# ups_main.net
KiCad netlist of a schematic drawn in EAGLE
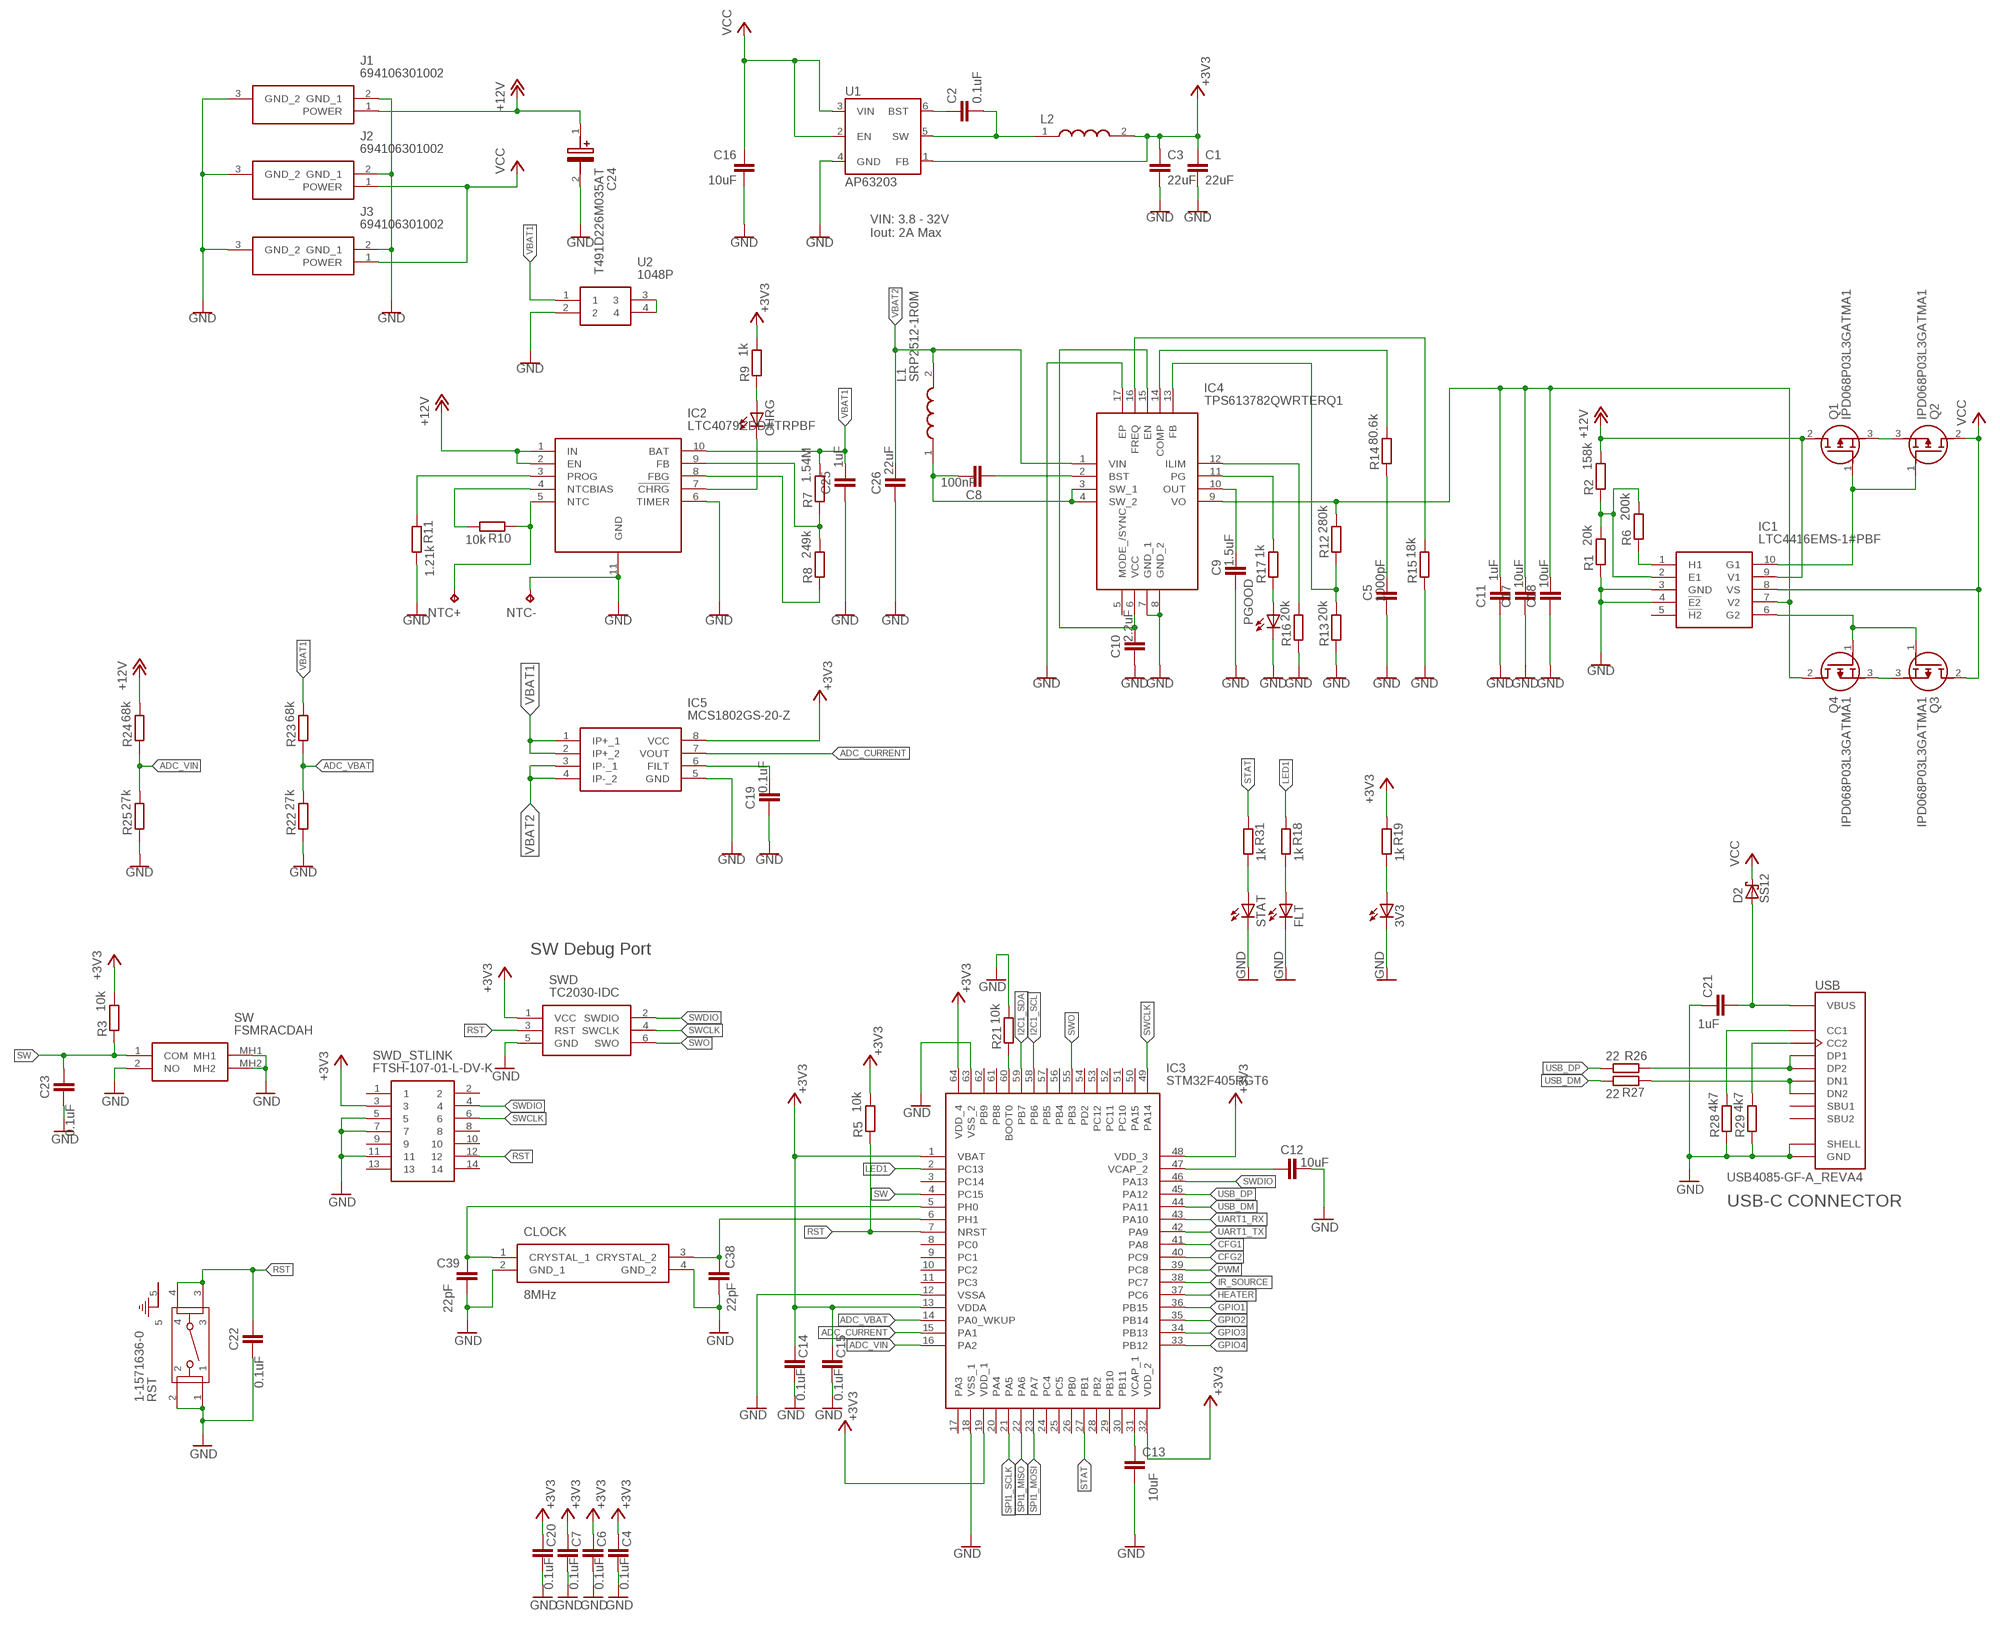
[diagram p0: schematic, sheet 1]

(export (version "E")
  (design (tool "Eeschema 10.0.6"))
  (components
    (comp (ref "3V3")
      (value "LEDCHIPLED_0805")
      (footprint "eagle-import:CHIPLED_0805")
      (libsource (lib "eagle-import") (part "LEDCHIPLED_0805"))
    )
    (comp (ref "C1")
      (value "22uF")
      (footprint "eagle-import:0603")
      (libsource (lib "eagle-import") (part "22UF-0603-6.3V-20%"))
    )
    (comp (ref "C2")
      (value "0.1uF")
      (footprint "eagle-import:0603")
      (libsource (lib "eagle-import") (part "0.1UF-0603-25V-5%"))
    )
    (comp (ref "C3")
      (value "22uF")
      (footprint "eagle-import:0603")
      (libsource (lib "eagle-import") (part "22UF-0603-6.3V-20%"))
    )
    (comp (ref "C4")
      (value "0.1uF")
      (footprint "eagle-import:C0603K")
      (libsource (lib "eagle-import") (part "C-EUC0603K"))
    )
    (comp (ref "C5")
      (value "1000pF")
      (footprint "eagle-import:C0603K")
      (libsource (lib "eagle-import") (part "C-EUC0603K"))
    )
    (comp (ref "C6")
      (value "0.1uF")
      (footprint "eagle-import:C0603K")
      (libsource (lib "eagle-import") (part "C-EUC0603K"))
    )
    (comp (ref "C7")
      (value "0.1uF")
      (footprint "eagle-import:C0603K")
      (libsource (lib "eagle-import") (part "C-EUC0603K"))
    )
    (comp (ref "C8")
      (value "100nF")
      (footprint "eagle-import:C0603K")
      (libsource (lib "eagle-import") (part "C-EUC0603K"))
    )
    (comp (ref "C9")
      (value "1.5uF")
      (footprint "eagle-import:C0603K")
      (libsource (lib "eagle-import") (part "C-EUC0603K"))
    )
    (comp (ref "C10")
      (value "2.2uF")
      (footprint "eagle-import:C0603K")
      (libsource (lib "eagle-import") (part "C-EUC0603K"))
    )
    (comp (ref "C11")
      (value "1uF")
      (footprint "eagle-import:C0603K")
      (libsource (lib "eagle-import") (part "C-EUC0603K"))
    )
    (comp (ref "C12")
      (value "10uF")
      (footprint "eagle-import:C0603K")
      (libsource (lib "eagle-import") (part "C-EUC0603K"))
    )
    (comp (ref "C13")
      (value "10uF")
      (footprint "eagle-import:C0603K")
      (libsource (lib "eagle-import") (part "C-EUC0603K"))
    )
    (comp (ref "C14")
      (value "0.1uF")
      (footprint "eagle-import:C0603K")
      (libsource (lib "eagle-import") (part "C-EUC0603K"))
    )
    (comp (ref "C15")
      (value "0.1uF")
      (footprint "eagle-import:C0603K")
      (libsource (lib "eagle-import") (part "C-EUC0603K"))
    )
    (comp (ref "C16")
      (value "10uF")
      (footprint "eagle-import:1210")
      (libsource (lib "eagle-import") (part "10UF-1210-50V-20%"))
    )
    (comp (ref "C17")
      (value "10uF")
      (footprint "eagle-import:C0603K")
      (libsource (lib "eagle-import") (part "C-EUC0603K"))
    )
    (comp (ref "C18")
      (value "10uF")
      (footprint "eagle-import:C0603K")
      (libsource (lib "eagle-import") (part "C-EUC0603K"))
    )
    (comp (ref "C19")
      (value "0.1uF")
      (footprint "eagle-import:C0603K")
      (libsource (lib "eagle-import") (part "C-EUC0603K"))
    )
    (comp (ref "C20")
      (value "0.1uF")
      (footprint "eagle-import:C0603K")
      (libsource (lib "eagle-import") (part "C-EUC0603K"))
    )
    (comp (ref "C21")
      (value "1uF")
      (footprint "eagle-import:C0603K")
      (libsource (lib "eagle-import") (part "C-EUC0603K"))
    )
    (comp (ref "C22")
      (value "0.1uF")
      (footprint "eagle-import:C0603K")
      (libsource (lib "eagle-import") (part "C-EUC0603K"))
    )
    (comp (ref "C23")
      (value "0.1uF")
      (footprint "eagle-import:C0603K")
      (libsource (lib "eagle-import") (part "C-EUC0603K"))
    )
    (comp (ref "C24")
      (value "T491D226M035AT")
      (footprint "eagle-import:T491D")
      (fields (field (name "MOUSER_PART_NUMBER") "80-T491D226M035"))
      (libsource (lib "eagle-import") (part "T491D226M035AT"))
    )
    (comp (ref "C25")
      (value "1uF")
      (footprint "eagle-import:C0603K")
      (libsource (lib "eagle-import") (part "C-EUC0603K"))
    )
    (comp (ref "C26")
      (value "22uF")
      (footprint "eagle-import:C0603K")
      (libsource (lib "eagle-import") (part "C-EUC0603K"))
    )
    (comp (ref "C38")
      (value "22pF")
      (footprint "eagle-import:C0603K")
      (libsource (lib "eagle-import") (part "C-EUC0603K"))
    )
    (comp (ref "C39")
      (value "22pF")
      (footprint "eagle-import:C0603K")
      (libsource (lib "eagle-import") (part "C-EUC0603K"))
    )
    (comp (ref "CHRG")
      (value "LEDCHIPLED_0805")
      (footprint "eagle-import:CHIPLED_0805")
      (libsource (lib "eagle-import") (part "LEDCHIPLED_0805"))
    )
    (comp (ref "CLOCK")
      (value "8MHz")
      (footprint "eagle-import:ABM8AIG8000MHZ1ZT")
      (fields
        (field (name "MANUFACTURER_PART_NUMBER") "ABM8AIG-8.000MHZ-1Z-T")
        (field (name "MOUSER_PART_NUMBER") "815-M8AIG-8-1ZT")
      )
      (libsource (lib "eagle-import") (part "ABM8AIG-8.000MHZ-1Z-T"))
    )
    (comp (ref "D2")
      (value "SS12")
      (footprint "eagle-import:DO214AC")
      (fields (field (name "MF") "Klein Tools,"))
      (libsource (lib "eagle-import") (part "SS12"))
    )
    (comp (ref "FLT")
      (value "LEDCHIPLED_0805")
      (footprint "eagle-import:CHIPLED_0805")
      (libsource (lib "eagle-import") (part "LEDCHIPLED_0805"))
    )
    (comp (ref "IC1")
      (value "LTC4416EMS-1#PBF")
      (footprint "eagle-import:SOP50P490X110-10N")
      (fields (field (name "MOUSER_PART_NUMBER") "584-LTC4416EMS-1#PBF"))
      (libsource (lib "eagle-import") (part "LTC4416EMS-1#PBF"))
    )
    (comp (ref "IC2")
      (value "LTC4079EDD#TRPBF")
      (footprint "eagle-import:SON50P300X300X80-11N")
      (fields (field (name "MOUSER_PART_NUMBER") "584-LTC4079EDD#TRPBF"))
      (libsource (lib "eagle-import") (part "LTC4079EDD#TRPBF"))
    )
    (comp (ref "IC3")
      (value "STM32F405RGT6")
      (footprint "eagle-import:QFP50P1200X1200X160-64N")
      (fields (field (name "MOUSER_PART_NUMBER") "511-STM32F405RGT6"))
      (libsource (lib "eagle-import") (part "STM32F405RGT6"))
    )
    (comp (ref "IC4")
      (value "TPS613782QWRTERQ1")
      (footprint "eagle-import:QFN50P300X300X80-17N")
      (fields
        (field (name "MANUFACTURER_PART_NUMBER") "TPS613783QWRTERQ1")
        (field (name "MOUSER_PART_NUMBER") "595-PS613783QWRTERQ1")
      )
      (libsource (lib "eagle-import") (part "TPS613783QWRTERQ1"))
    )
    (comp (ref "IC5")
      (value "MCS1802GS-20-Z")
      (footprint "eagle-import:SOIC127P600X175-8N")
      (fields (field (name "MOUSER_PART_NUMBER") "946-MCS1802GS-20-Z"))
      (libsource (lib "eagle-import") (part "MCS1802GS-20-Z"))
    )
    (comp (ref "J1")
      (value "694106301002")
      (footprint "eagle-import:694106301002_1")
      (fields (field (name "MOUSER_PART_NUMBER") "710-694106301002"))
      (libsource (lib "eagle-import") (part "694106301002"))
    )
    (comp (ref "J2")
      (value "694106301002")
      (footprint "eagle-import:694106301002_1")
      (fields (field (name "MOUSER_PART_NUMBER") "710-694106301002"))
      (libsource (lib "eagle-import") (part "694106301002"))
    )
    (comp (ref "J3")
      (value "694106301002")
      (footprint "eagle-import:694106301002_1")
      (fields (field (name "MOUSER_PART_NUMBER") "710-694106301002"))
      (libsource (lib "eagle-import") (part "694106301002"))
    )
    (comp (ref "L1")
      (value "SRP2512-1R0M")
      (footprint "eagle-import:INDC2520X120N")
      (fields (field (name "MOUSER_PART_NUMBER") "652-SRP2512-1R0M"))
      (libsource (lib "eagle-import") (part "SRP2512-1R0M"))
    )
    (comp (ref "L2")
      (value "MLZ2012M4R7HT000")
      (footprint "eagle-import:INDC2012X145N")
      (fields (field (name "MOUSER_PART_NUMBER") "810-MLZ2012M4R7HT000"))
      (libsource (lib "eagle-import") (part "MLZ2012M4R7HT000"))
    )
    (comp (ref "NTC+")
      (value "TPPAD1-17")
      (footprint "eagle-import:P1-17")
      (libsource (lib "eagle-import") (part "TPPAD1-17"))
    )
    (comp (ref "NTC-")
      (value "TPPAD1-17")
      (footprint "eagle-import:P1-17")
      (libsource (lib "eagle-import") (part "TPPAD1-17"))
    )
    (comp (ref "PGOOD")
      (value "LEDCHIPLED_0805")
      (footprint "eagle-import:CHIPLED_0805")
      (libsource (lib "eagle-import") (part "LEDCHIPLED_0805"))
    )
    (comp (ref "Q1")
      (value "IPD068P03L3GATMA1")
      (footprint "eagle-import:IPD068P03L3GATMA1")
      (fields (field (name "MOUSER_PART_NUMBER") "726-IPD068P03L3GATMA"))
      (libsource (lib "eagle-import") (part "IPD068P03L3GATMA1"))
    )
    (comp (ref "Q2")
      (value "IPD068P03L3GATMA1")
      (footprint "eagle-import:IPD068P03L3GATMA1")
      (fields (field (name "MOUSER_PART_NUMBER") "726-IPD068P03L3GATMA"))
      (libsource (lib "eagle-import") (part "IPD068P03L3GATMA1"))
    )
    (comp (ref "Q3")
      (value "IPD068P03L3GATMA1")
      (footprint "eagle-import:IPD068P03L3GATMA1")
      (fields (field (name "MOUSER_PART_NUMBER") "726-IPD068P03L3GATMA"))
      (libsource (lib "eagle-import") (part "IPD068P03L3GATMA1"))
    )
    (comp (ref "Q4")
      (value "IPD068P03L3GATMA1")
      (footprint "eagle-import:IPD068P03L3GATMA1")
      (fields (field (name "MOUSER_PART_NUMBER") "726-IPD068P03L3GATMA"))
      (libsource (lib "eagle-import") (part "IPD068P03L3GATMA1"))
    )
    (comp (ref "R1")
      (value "20k")
      (footprint "eagle-import:R0603")
      (libsource (lib "eagle-import") (part "R-EU_R0603"))
    )
    (comp (ref "R2")
      (value "158k")
      (footprint "eagle-import:R0603")
      (libsource (lib "eagle-import") (part "R-EU_R0603"))
    )
    (comp (ref "R3")
      (value "10k")
      (footprint "eagle-import:R0603")
      (libsource (lib "eagle-import") (part "R-EU_R0603"))
    )
    (comp (ref "R5")
      (value "10k")
      (footprint "eagle-import:R0603")
      (libsource (lib "eagle-import") (part "R-EU_R0603"))
    )
    (comp (ref "R6")
      (value "200k")
      (footprint "eagle-import:R0603")
      (libsource (lib "eagle-import") (part "R-EU_R0603"))
    )
    (comp (ref "R7")
      (value "1.54M")
      (footprint "eagle-import:R0603")
      (libsource (lib "eagle-import") (part "R-EU_R0603"))
    )
    (comp (ref "R8")
      (value "249k")
      (footprint "eagle-import:R0603")
      (libsource (lib "eagle-import") (part "R-EU_R0603"))
    )
    (comp (ref "R9")
      (value "1k")
      (footprint "eagle-import:R0603")
      (libsource (lib "eagle-import") (part "R-EU_R0603"))
    )
    (comp (ref "R10")
      (value "10k")
      (footprint "eagle-import:R0603")
      (libsource (lib "eagle-import") (part "R-EU_R0603"))
    )
    (comp (ref "R11")
      (value "1.21k")
      (footprint "eagle-import:R0603")
      (libsource (lib "eagle-import") (part "R-EU_R0603"))
    )
    (comp (ref "R12")
      (value "280k")
      (footprint "eagle-import:R0603")
      (libsource (lib "eagle-import") (part "R-EU_R0603"))
    )
    (comp (ref "R13")
      (value "20k")
      (footprint "eagle-import:R0603")
      (libsource (lib "eagle-import") (part "R-EU_R0603"))
    )
    (comp (ref "R14")
      (value "80.6k")
      (footprint "eagle-import:R0603")
      (libsource (lib "eagle-import") (part "R-EU_R0603"))
    )
    (comp (ref "R15")
      (value "18k")
      (footprint "eagle-import:R0603")
      (libsource (lib "eagle-import") (part "R-EU_R0603"))
    )
    (comp (ref "R16")
      (value "20k")
      (footprint "eagle-import:R0603")
      (libsource (lib "eagle-import") (part "R-EU_R0603"))
    )
    (comp (ref "R17")
      (value "1k")
      (footprint "eagle-import:R0603")
      (libsource (lib "eagle-import") (part "R-EU_R0603"))
    )
    (comp (ref "R18")
      (value "1k")
      (footprint "eagle-import:R0603")
      (libsource (lib "eagle-import") (part "R-EU_R0603"))
    )
    (comp (ref "R19")
      (value "1k")
      (footprint "eagle-import:R0603")
      (libsource (lib "eagle-import") (part "R-EU_R0603"))
    )
    (comp (ref "R21")
      (value "10k")
      (footprint "eagle-import:R0603")
      (libsource (lib "eagle-import") (part "R-EU_R0603"))
    )
    (comp (ref "R22")
      (value "27k")
      (footprint "eagle-import:R0603")
      (libsource (lib "eagle-import") (part "R-EU_R0603"))
    )
    (comp (ref "R23")
      (value "68k")
      (footprint "eagle-import:R0603")
      (libsource (lib "eagle-import") (part "R-EU_R0603"))
    )
    (comp (ref "R24")
      (value "68k")
      (footprint "eagle-import:R0603")
      (libsource (lib "eagle-import") (part "R-EU_R0603"))
    )
    (comp (ref "R25")
      (value "27k")
      (footprint "eagle-import:R0603")
      (libsource (lib "eagle-import") (part "R-EU_R0603"))
    )
    (comp (ref "R26")
      (value "22")
      (footprint "eagle-import:R0603")
      (libsource (lib "eagle-import") (part "R-EU_R0603"))
    )
    (comp (ref "R27")
      (value "22")
      (footprint "eagle-import:R0603")
      (libsource (lib "eagle-import") (part "R-EU_R0603"))
    )
    (comp (ref "R28")
      (value "4k7")
      (footprint "eagle-import:R0603")
      (libsource (lib "eagle-import") (part "R-EU_R0603"))
    )
    (comp (ref "R29")
      (value "4k7")
      (footprint "eagle-import:R0603")
      (libsource (lib "eagle-import") (part "R-EU_R0603"))
    )
    (comp (ref "R31")
      (value "1k")
      (footprint "eagle-import:R0603")
      (libsource (lib "eagle-import") (part "R-EU_R0603"))
    )
    (comp (ref "RST")
      (value "1-1571636-0")
      (footprint "eagle-import:SW5_1571636")
      (fields (field (name "COPYRIGHT") "Copyright (C) 2016 Accelerated Designs. All rights reserved"))
      (libsource (lib "eagle-import") (part "1-1571636-0"))
    )
    (comp (ref "STAT")
      (value "LEDCHIPLED_0805")
      (footprint "eagle-import:CHIPLED_0805")
      (libsource (lib "eagle-import") (part "LEDCHIPLED_0805"))
    )
    (comp (ref "SW")
      (value "FSMRACDAH")
      (footprint "eagle-import:FSMRACDAH")
      (fields (field (name "MOUSER_PART_NUMBER") "506-FSMRACDAH"))
      (libsource (lib "eagle-import") (part "FSMRACDAH"))
    )
    (comp (ref "SWD")
      (value "TC2030-IDC")
      (footprint "eagle-import:TC2030IDC")
      (libsource (lib "eagle-import") (part "TC2030-IDC"))
    )
    (comp (ref "SWD_STLINK")
      (value "FTSH-107-01-L-DV-K")
      (footprint "eagle-import:FTSH-107-XX-YYY-DV-K")
      (fields (field (name "MOUSER_PART_NUMBER") "200-FTSH10701LDVK"))
      (libsource (lib "eagle-import") (part "FTSH-107-01-L-DV-K"))
    )
    (comp (ref "U1")
      (value "AP63203")
      (footprint "eagle-import:SOT23-6")
      (libsource (lib "eagle-import") (part "AP63203"))
    )
    (comp (ref "U2")
      (value "1048P")
      (footprint "eagle-import:1048P")
      (fields (field (name "MOUSER_PART_NUMBER") "534-1048P"))
      (libsource (lib "eagle-import") (part "1048P"))
    )
    (comp (ref "USB")
      (value "USB4085-GF-A_REVA4")
      (footprint "eagle-import:GCT_USB4085-GF-A_REVA4")
      (fields (field (name "MF") "Global Connector Technology") (field (name "MP") "USB4085-GF-A"))
      (libsource (lib "eagle-import") (part "USB4085-GF-A_REVA4"))
    )
  )
  (nets
    (net (code "1") (name "+3V3") (class "Default")
      (node (ref "C1") (pin "1") (pinfunction "1_1") (pintype "passive"))
      (node (ref "C14") (pin "1") (pinfunction "1_1") (pintype "passive"))
      (node (ref "C15") (pin "1") (pinfunction "1_1") (pintype "passive"))
      (node (ref "C20") (pin "1") (pinfunction "1_1") (pintype "passive"))
      (node (ref "C3") (pin "1") (pinfunction "1_1") (pintype "passive"))
      (node (ref "C4") (pin "1") (pinfunction "1_1") (pintype "passive"))
      (node (ref "C6") (pin "1") (pinfunction "1_1") (pintype "passive"))
      (node (ref "C7") (pin "1") (pinfunction "1_1") (pintype "passive"))
      (node (ref "IC3") (pin "1") (pinfunction "VBAT_1") (pintype "bidirectional"))
      (node (ref "IC3") (pin "13") (pinfunction "VDDA_13") (pintype "bidirectional"))
      (node (ref "IC3") (pin "19") (pinfunction "VDD_1_19") (pintype "bidirectional"))
      (node (ref "IC3") (pin "32") (pinfunction "VDD_2_32") (pintype "bidirectional"))
      (node (ref "IC3") (pin "48") (pinfunction "VDD_3_48") (pintype "bidirectional"))
      (node (ref "IC3") (pin "64") (pinfunction "VDD_4_64") (pintype "bidirectional"))
      (node (ref "IC5") (pin "8") (pinfunction "VCC_8") (pintype "bidirectional"))
      (node (ref "L2") (pin "2") (pinfunction "2_2") (pintype "bidirectional"))
      (node (ref "R19") (pin "1") (pinfunction "1_1") (pintype "passive"))
      (node (ref "R3") (pin "2") (pinfunction "2_2") (pintype "passive"))
      (node (ref "R5") (pin "2") (pinfunction "2_2") (pintype "passive"))
      (node (ref "R9") (pin "2") (pinfunction "2_2") (pintype "passive"))
      (node (ref "SWD") (pin "1") (pinfunction "VCC_1") (pintype "bidirectional"))
      (node (ref "SWD_STLINK") (pin "3") (pinfunction "3_3") (pintype "bidirectional"))
      (node (ref "U1") (pin "1") (pinfunction "FB_1") (pintype "bidirectional"))
    )
    (net (code "2") (name "+12V") (class "Default")
      (node (ref "C24") (pin "1") (pinfunction "+_1") (pintype "bidirectional"))
      (node (ref "IC1") (pin "9") (pinfunction "V1_9") (pintype "bidirectional"))
      (node (ref "IC2") (pin "1") (pinfunction "IN_1") (pintype "bidirectional"))
      (node (ref "IC2") (pin "2") (pinfunction "EN_2") (pintype "bidirectional"))
      (node (ref "J1") (pin "1") (pinfunction "POWER_1") (pintype "bidirectional"))
      (node (ref "Q1") (pin "2") (pinfunction "D_2") (pintype "bidirectional"))
      (node (ref "R2") (pin "2") (pinfunction "2_2") (pintype "passive"))
      (node (ref "R24") (pin "2") (pinfunction "2_2") (pintype "passive"))
    )
    (net (code "3") (name "ADC_CURRENT") (class "Default")
      (node (ref "IC3") (pin "15") (pinfunction "PA1_15") (pintype "bidirectional"))
      (node (ref "IC5") (pin "7") (pinfunction "VOUT_7") (pintype "bidirectional"))
    )
    (net (code "4") (name "ADC_VBAT") (class "Default")
      (node (ref "IC3") (pin "14") (pinfunction "PA0_WKUP_14") (pintype "bidirectional"))
      (node (ref "R22") (pin "2") (pinfunction "2_2") (pintype "passive"))
      (node (ref "R23") (pin "1") (pinfunction "1_1") (pintype "passive"))
    )
    (net (code "5") (name "ADC_VIN") (class "Default")
      (node (ref "IC3") (pin "16") (pinfunction "PA2_16") (pintype "bidirectional"))
      (node (ref "R24") (pin "1") (pinfunction "1_1") (pintype "passive"))
      (node (ref "R25") (pin "2") (pinfunction "2_2") (pintype "passive"))
    )
    (net (code "6") (name "CFG1") (class "Default")
      (node (ref "IC3") (pin "41") (pinfunction "PA8_41") (pintype "bidirectional"))
    )
    (net (code "7") (name "CFG2") (class "Default")
      (node (ref "IC3") (pin "40") (pinfunction "PC9_40") (pintype "bidirectional"))
    )
    (net (code "8") (name "GND") (class "Default")
      (node (ref "3V3") (pin "C") (pinfunction "C_C") (pintype "passive"))
      (node (ref "C1") (pin "2") (pinfunction "2_2") (pintype "passive"))
      (node (ref "C10") (pin "1") (pinfunction "1_1") (pintype "passive"))
      (node (ref "C11") (pin "1") (pinfunction "1_1") (pintype "passive"))
      (node (ref "C12") (pin "2") (pinfunction "2_2") (pintype "passive"))
      (node (ref "C13") (pin "2") (pinfunction "2_2") (pintype "passive"))
      (node (ref "C14") (pin "2") (pinfunction "2_2") (pintype "passive"))
      (node (ref "C15") (pin "2") (pinfunction "2_2") (pintype "passive"))
      (node (ref "C16") (pin "2") (pinfunction "2_2") (pintype "passive"))
      (node (ref "C17") (pin "1") (pinfunction "1_1") (pintype "passive"))
      (node (ref "C18") (pin "1") (pinfunction "1_1") (pintype "passive"))
      (node (ref "C19") (pin "1") (pinfunction "1_1") (pintype "passive"))
      (node (ref "C20") (pin "2") (pinfunction "2_2") (pintype "passive"))
      (node (ref "C21") (pin "1") (pinfunction "1_1") (pintype "passive"))
      (node (ref "C22") (pin "2") (pinfunction "2_2") (pintype "passive"))
      (node (ref "C23") (pin "2") (pinfunction "2_2") (pintype "passive"))
      (node (ref "C24") (pin "2") (pinfunction "-_2") (pintype "bidirectional"))
      (node (ref "C25") (pin "1") (pinfunction "1_1") (pintype "passive"))
      (node (ref "C26") (pin "1") (pinfunction "1_1") (pintype "passive"))
      (node (ref "C3") (pin "2") (pinfunction "2_2") (pintype "passive"))
      (node (ref "C38") (pin "2") (pinfunction "2_2") (pintype "passive"))
      (node (ref "C39") (pin "2") (pinfunction "2_2") (pintype "passive"))
      (node (ref "C4") (pin "2") (pinfunction "2_2") (pintype "passive"))
      (node (ref "C5") (pin "1") (pinfunction "1_1") (pintype "passive"))
      (node (ref "C6") (pin "2") (pinfunction "2_2") (pintype "passive"))
      (node (ref "C7") (pin "2") (pinfunction "2_2") (pintype "passive"))
      (node (ref "C9") (pin "1") (pinfunction "1_1") (pintype "passive"))
      (node (ref "CLOCK") (pin "2") (pinfunction "GND_1_2") (pintype "bidirectional"))
      (node (ref "CLOCK") (pin "4") (pinfunction "GND_2_4") (pintype "bidirectional"))
      (node (ref "FLT") (pin "C") (pinfunction "C_C") (pintype "passive"))
      (node (ref "IC1") (pin "3") (pinfunction "GND_3") (pintype "bidirectional"))
      (node (ref "IC1") (pin "4") (pinfunction "~{E2}_4") (pintype "bidirectional"))
      (node (ref "IC2") (pin "11") (pinfunction "GND_11") (pintype "bidirectional"))
      (node (ref "IC2") (pin "6") (pinfunction "TIMER_6") (pintype "bidirectional"))
      (node (ref "IC3") (pin "12") (pinfunction "VSSA_12") (pintype "bidirectional"))
      (node (ref "IC3") (pin "18") (pinfunction "VSS_1_18") (pintype "bidirectional"))
      (node (ref "IC3") (pin "63") (pinfunction "VSS_2_63") (pintype "bidirectional"))
      (node (ref "IC4") (pin "17") (pinfunction "EP_17") (pintype "bidirectional"))
      (node (ref "IC4") (pin "7") (pinfunction "GND_1_7") (pintype "bidirectional"))
      (node (ref "IC4") (pin "8") (pinfunction "GND_2_8") (pintype "bidirectional"))
      (node (ref "IC5") (pin "5") (pinfunction "GND_5") (pintype "bidirectional"))
      (node (ref "J1") (pin "2") (pinfunction "GND_1_2") (pintype "bidirectional"))
      (node (ref "J1") (pin "3") (pinfunction "GND_2_3") (pintype "bidirectional"))
      (node (ref "J2") (pin "2") (pinfunction "GND_1_2") (pintype "bidirectional"))
      (node (ref "J2") (pin "3") (pinfunction "GND_2_3") (pintype "bidirectional"))
      (node (ref "J3") (pin "2") (pinfunction "GND_1_2") (pintype "bidirectional"))
      (node (ref "J3") (pin "3") (pinfunction "GND_2_3") (pintype "bidirectional"))
      (node (ref "NTC-") (pin "TP") (pinfunction "TP_TP") (pintype "input"))
      (node (ref "PGOOD") (pin "C") (pinfunction "C_C") (pintype "passive"))
      (node (ref "R1") (pin "1") (pinfunction "1_1") (pintype "passive"))
      (node (ref "R11") (pin "2") (pinfunction "2_2") (pintype "passive"))
      (node (ref "R13") (pin "1") (pinfunction "1_1") (pintype "passive"))
      (node (ref "R15") (pin "1") (pinfunction "1_1") (pintype "passive"))
      (node (ref "R16") (pin "1") (pinfunction "1_1") (pintype "passive"))
      (node (ref "R21") (pin "2") (pinfunction "2_2") (pintype "passive"))
      (node (ref "R22") (pin "1") (pinfunction "1_1") (pintype "passive"))
      (node (ref "R25") (pin "1") (pinfunction "1_1") (pintype "passive"))
      (node (ref "R28") (pin "1") (pinfunction "1_1") (pintype "passive"))
      (node (ref "R29") (pin "1") (pinfunction "1_1") (pintype "passive"))
      (node (ref "RST") (pin "1") (pinfunction "1_1") (pintype "passive"))
      (node (ref "RST") (pin "2") (pinfunction "2_2") (pintype "passive"))
      (node (ref "STAT") (pin "C") (pinfunction "C_C") (pintype "passive"))
      (node (ref "SW") (pin "2") (pinfunction "NO_2") (pintype "bidirectional"))
      (node (ref "SW") (pin "MH1") (pinfunction "MH1_MH1") (pintype "bidirectional"))
      (node (ref "SW") (pin "MH2") (pinfunction "MH2_MH2") (pintype "bidirectional"))
      (node (ref "SWD") (pin "5") (pinfunction "GND_5") (pintype "bidirectional"))
      (node (ref "SWD_STLINK") (pin "11") (pinfunction "11_11") (pintype "bidirectional"))
      (node (ref "SWD_STLINK") (pin "5") (pinfunction "5_5") (pintype "bidirectional"))
      (node (ref "SWD_STLINK") (pin "7") (pinfunction "7_7") (pintype "bidirectional"))
      (node (ref "U1") (pin "4") (pinfunction "GND_4") (pintype "bidirectional"))
      (node (ref "U2") (pin "2") (pinfunction "2_2") (pintype "bidirectional"))
      (node (ref "USB") (pin "A1") (pinfunction "GND_A1") (pintype "passive"))
      (node (ref "USB") (pin "A12") (pinfunction "GND_A12") (pintype "passive"))
      (node (ref "USB") (pin "B1") (pinfunction "GND_B1") (pintype "passive"))
      (node (ref "USB") (pin "B12") (pinfunction "GND_B12") (pintype "passive"))
      (node (ref "USB") (pin "P1") (pinfunction "SHELL_P1") (pintype "passive"))
      (node (ref "USB") (pin "P2") (pinfunction "SHELL_P2") (pintype "passive"))
      (node (ref "USB") (pin "P3") (pinfunction "SHELL_P3") (pintype "passive"))
      (node (ref "USB") (pin "P4") (pinfunction "SHELL_P4") (pintype "passive"))
    )
    (net (code "9") (name "GPIO1") (class "Default")
      (node (ref "IC3") (pin "36") (pinfunction "PB15_36") (pintype "bidirectional"))
    )
    (net (code "10") (name "GPIO2") (class "Default")
      (node (ref "IC3") (pin "35") (pinfunction "PB14_35") (pintype "bidirectional"))
    )
    (net (code "11") (name "GPIO3") (class "Default")
      (node (ref "IC3") (pin "34") (pinfunction "PB13_34") (pintype "bidirectional"))
    )
    (net (code "12") (name "GPIO4") (class "Default")
      (node (ref "IC3") (pin "33") (pinfunction "PB12_33") (pintype "bidirectional"))
    )
    (net (code "13") (name "HEATER") (class "Default")
      (node (ref "IC3") (pin "37") (pinfunction "PC6_37") (pintype "bidirectional"))
    )
    (net (code "14") (name "I2C1_SCL") (class "Default")
      (node (ref "IC3") (pin "58") (pinfunction "PB6_58") (pintype "bidirectional"))
    )
    (net (code "15") (name "I2C1_SDA") (class "Default")
      (node (ref "IC3") (pin "59") (pinfunction "PB7_59") (pintype "bidirectional"))
    )
    (net (code "16") (name "IR_SOURCE") (class "Default")
      (node (ref "IC3") (pin "38") (pinfunction "PC7_38") (pintype "bidirectional"))
    )
    (net (code "17") (name "LED1") (class "Default")
      (node (ref "IC3") (pin "2") (pinfunction "PC13_2") (pintype "bidirectional"))
      (node (ref "R18") (pin "1") (pinfunction "1_1") (pintype "passive"))
    )
    (net (code "18") (name "Net-(3V3-PadA)") (class "Default")
      (node (ref "3V3") (pin "A") (pinfunction "A_A") (pintype "passive"))
      (node (ref "R19") (pin "2") (pinfunction "2_2") (pintype "passive"))
    )
    (net (code "19") (name "Net-(C5-Pad2)") (class "Default")
      (node (ref "C5") (pin "2") (pinfunction "2_2") (pintype "passive"))
      (node (ref "R14") (pin "1") (pinfunction "1_1") (pintype "passive"))
    )
    (net (code "20") (name "Net-(C21-Pad2)") (class "Default")
      (node (ref "C21") (pin "2") (pinfunction "2_2") (pintype "passive"))
      (node (ref "D2") (pin "A") (pinfunction "A_A") (pintype "passive"))
      (node (ref "USB") (pin "A4") (pinfunction "VBUS_A4") (pintype "power_in"))
      (node (ref "USB") (pin "A9") (pinfunction "VBUS_A9") (pintype "power_in"))
      (node (ref "USB") (pin "B4") (pinfunction "VBUS_B4") (pintype "power_in"))
      (node (ref "USB") (pin "B9") (pinfunction "VBUS_B9") (pintype "power_in"))
    )
    (net (code "21") (name "Net-(CHRG-PadA)") (class "Default")
      (node (ref "CHRG") (pin "A") (pinfunction "A_A") (pintype "passive"))
      (node (ref "R9") (pin "1") (pinfunction "1_1") (pintype "passive"))
    )
    (net (code "22") (name "Net-(CLOCK-CRYSTAL_1)") (class "Default")
      (node (ref "C39") (pin "1") (pinfunction "1_1") (pintype "passive"))
      (node (ref "CLOCK") (pin "1") (pinfunction "CRYSTAL_1_1") (pintype "bidirectional"))
      (node (ref "IC3") (pin "5") (pinfunction "PH0_5") (pintype "bidirectional"))
    )
    (net (code "23") (name "Net-(CLOCK-CRYSTAL_2)") (class "Default")
      (node (ref "C38") (pin "1") (pinfunction "1_1") (pintype "passive"))
      (node (ref "CLOCK") (pin "3") (pinfunction "CRYSTAL_2_3") (pintype "bidirectional"))
      (node (ref "IC3") (pin "6") (pinfunction "PH1_6") (pintype "bidirectional"))
    )
    (net (code "24") (name "Net-(FLT-PadA)") (class "Default")
      (node (ref "FLT") (pin "A") (pinfunction "A_A") (pintype "passive"))
      (node (ref "R18") (pin "2") (pinfunction "2_2") (pintype "passive"))
    )
    (net (code "25") (name "Net-(IC1-E1)") (class "Default")
      (node (ref "IC1") (pin "2") (pinfunction "E1_2") (pintype "bidirectional"))
      (node (ref "R1") (pin "2") (pinfunction "2_2") (pintype "passive"))
      (node (ref "R2") (pin "1") (pinfunction "1_1") (pintype "passive"))
      (node (ref "R6") (pin "2") (pinfunction "2_2") (pintype "passive"))
    )
    (net (code "26") (name "Net-(IC1-G1)") (class "Default")
      (node (ref "IC1") (pin "10") (pinfunction "G1_10") (pintype "bidirectional"))
      (node (ref "Q1") (pin "1") (pinfunction "G_1") (pintype "bidirectional"))
      (node (ref "Q2") (pin "1") (pinfunction "G_1") (pintype "bidirectional"))
    )
    (net (code "27") (name "Net-(IC1-G2)") (class "Default")
      (node (ref "IC1") (pin "6") (pinfunction "G2_6") (pintype "bidirectional"))
      (node (ref "Q3") (pin "1") (pinfunction "G_1") (pintype "bidirectional"))
      (node (ref "Q4") (pin "1") (pinfunction "G_1") (pintype "bidirectional"))
    )
    (net (code "28") (name "Net-(IC1-H1)") (class "Default")
      (node (ref "IC1") (pin "1") (pinfunction "H1_1") (pintype "bidirectional"))
      (node (ref "R6") (pin "1") (pinfunction "1_1") (pintype "passive"))
    )
    (net (code "29") (name "Net-(IC1-V2)") (class "Default")
      (node (ref "C11") (pin "2") (pinfunction "2_2") (pintype "passive"))
      (node (ref "C17") (pin "2") (pinfunction "2_2") (pintype "passive"))
      (node (ref "C18") (pin "2") (pinfunction "2_2") (pintype "passive"))
      (node (ref "IC1") (pin "7") (pinfunction "V2_7") (pintype "bidirectional"))
      (node (ref "IC4") (pin "9") (pinfunction "VO_9") (pintype "bidirectional"))
      (node (ref "Q4") (pin "2") (pinfunction "D_2") (pintype "bidirectional"))
      (node (ref "R12") (pin "2") (pinfunction "2_2") (pintype "passive"))
    )
    (net (code "30") (name "Net-(IC2-FB)") (class "Default")
      (node (ref "IC2") (pin "9") (pinfunction "FB_9") (pintype "bidirectional"))
      (node (ref "R7") (pin "1") (pinfunction "1_1") (pintype "passive"))
      (node (ref "R8") (pin "2") (pinfunction "2_2") (pintype "passive"))
    )
    (net (code "31") (name "Net-(IC2-FBG)") (class "Default")
      (node (ref "IC2") (pin "8") (pinfunction "FBG_8") (pintype "bidirectional"))
      (node (ref "R8") (pin "1") (pinfunction "1_1") (pintype "passive"))
    )
    (net (code "32") (name "Net-(IC2-NTC)") (class "Default")
      (node (ref "IC2") (pin "5") (pinfunction "NTC_5") (pintype "bidirectional"))
      (node (ref "NTC+") (pin "TP") (pinfunction "TP_TP") (pintype "input"))
      (node (ref "R10") (pin "1") (pinfunction "1_1") (pintype "passive"))
    )
    (net (code "33") (name "Net-(IC2-NTCBIAS)") (class "Default")
      (node (ref "IC2") (pin "4") (pinfunction "NTCBIAS_4") (pintype "bidirectional"))
      (node (ref "R10") (pin "2") (pinfunction "2_2") (pintype "passive"))
    )
    (net (code "34") (name "Net-(IC2-PROG)") (class "Default")
      (node (ref "IC2") (pin "3") (pinfunction "PROG_3") (pintype "bidirectional"))
      (node (ref "R11") (pin "1") (pinfunction "1_1") (pintype "passive"))
    )
    (net (code "35") (name "Net-(IC2-~{CHRG})") (class "Default")
      (node (ref "CHRG") (pin "C") (pinfunction "C_C") (pintype "passive"))
      (node (ref "IC2") (pin "7") (pinfunction "~{CHRG}_7") (pintype "bidirectional"))
    )
    (net (code "36") (name "Net-(IC3-BOOT0)") (class "Default")
      (node (ref "IC3") (pin "60") (pinfunction "BOOT0_60") (pintype "bidirectional"))
      (node (ref "R21") (pin "1") (pinfunction "1_1") (pintype "passive"))
    )
    (net (code "37") (name "Net-(IC3-VCAP_1)") (class "Default")
      (node (ref "C13") (pin "1") (pinfunction "1_1") (pintype "passive"))
      (node (ref "IC3") (pin "31") (pinfunction "VCAP_1_31") (pintype "bidirectional"))
    )
    (net (code "38") (name "Net-(IC3-VCAP_2)") (class "Default")
      (node (ref "C12") (pin "1") (pinfunction "1_1") (pintype "passive"))
      (node (ref "IC3") (pin "47") (pinfunction "VCAP_2_47") (pintype "bidirectional"))
    )
    (net (code "39") (name "Net-(IC4-BST)") (class "Default")
      (node (ref "C8") (pin "1") (pinfunction "1_1") (pintype "passive"))
      (node (ref "IC4") (pin "2") (pinfunction "BST_2") (pintype "bidirectional"))
    )
    (net (code "40") (name "Net-(IC4-COMP)") (class "Default")
      (node (ref "IC4") (pin "14") (pinfunction "COMP_14") (pintype "bidirectional"))
      (node (ref "R14") (pin "2") (pinfunction "2_2") (pintype "passive"))
    )
    (net (code "41") (name "Net-(IC4-EN)") (class "Default")
      (node (ref "C10") (pin "2") (pinfunction "2_2") (pintype "passive"))
      (node (ref "IC4") (pin "15") (pinfunction "EN_15") (pintype "bidirectional"))
      (node (ref "IC4") (pin "6") (pinfunction "VCC_6") (pintype "bidirectional"))
    )
    (net (code "42") (name "Net-(IC4-FB)") (class "Default")
      (node (ref "IC4") (pin "13") (pinfunction "FB_13") (pintype "bidirectional"))
      (node (ref "R12") (pin "1") (pinfunction "1_1") (pintype "passive"))
      (node (ref "R13") (pin "2") (pinfunction "2_2") (pintype "passive"))
    )
    (net (code "43") (name "Net-(IC4-FREQ)") (class "Default")
      (node (ref "IC4") (pin "16") (pinfunction "FREQ_16") (pintype "bidirectional"))
      (node (ref "R15") (pin "2") (pinfunction "2_2") (pintype "passive"))
    )
    (net (code "44") (name "Net-(IC4-ILIM)") (class "Default")
      (node (ref "IC4") (pin "12") (pinfunction "ILIM_12") (pintype "bidirectional"))
      (node (ref "R16") (pin "2") (pinfunction "2_2") (pintype "passive"))
    )
    (net (code "45") (name "Net-(IC4-OUT)") (class "Default")
      (node (ref "C9") (pin "2") (pinfunction "2_2") (pintype "passive"))
      (node (ref "IC4") (pin "10") (pinfunction "OUT_10") (pintype "bidirectional"))
    )
    (net (code "46") (name "Net-(IC4-PG)") (class "Default")
      (node (ref "IC4") (pin "11") (pinfunction "PG_11") (pintype "bidirectional"))
      (node (ref "R17") (pin "2") (pinfunction "2_2") (pintype "passive"))
    )
    (net (code "47") (name "Net-(IC4-SW_1)") (class "Default")
      (node (ref "C8") (pin "2") (pinfunction "2_2") (pintype "passive"))
      (node (ref "IC4") (pin "3") (pinfunction "SW_1_3") (pintype "bidirectional"))
      (node (ref "IC4") (pin "4") (pinfunction "SW_2_4") (pintype "bidirectional"))
      (node (ref "L1") (pin "1") (pinfunction "1_1") (pintype "bidirectional"))
    )
    (net (code "48") (name "Net-(IC5-FILT)") (class "Default")
      (node (ref "C19") (pin "2") (pinfunction "2_2") (pintype "passive"))
      (node (ref "IC5") (pin "6") (pinfunction "FILT_6") (pintype "bidirectional"))
    )
    (net (code "49") (name "Net-(PGOOD-PadA)") (class "Default")
      (node (ref "PGOOD") (pin "A") (pinfunction "A_A") (pintype "passive"))
      (node (ref "R17") (pin "1") (pinfunction "1_1") (pintype "passive"))
    )
    (net (code "50") (name "Net-(Q1-S)") (class "Default")
      (node (ref "Q1") (pin "3") (pinfunction "S_3") (pintype "bidirectional"))
      (node (ref "Q2") (pin "3") (pinfunction "S_3") (pintype "bidirectional"))
    )
    (net (code "51") (name "Net-(Q3-S)") (class "Default")
      (node (ref "Q3") (pin "3") (pinfunction "S_3") (pintype "bidirectional"))
      (node (ref "Q4") (pin "3") (pinfunction "S_3") (pintype "bidirectional"))
    )
    (net (code "52") (name "Net-(R31-Pad2)") (class "Default")
      (node (ref "R31") (pin "2") (pinfunction "2_2") (pintype "passive"))
      (node (ref "STAT") (pin "A") (pinfunction "A_A") (pintype "passive"))
    )
    (net (code "53") (name "Net-(U1-BST)") (class "Default")
      (node (ref "C2") (pin "1") (pinfunction "1_1") (pintype "passive"))
      (node (ref "U1") (pin "6") (pinfunction "BST_6") (pintype "bidirectional"))
    )
    (net (code "54") (name "Net-(U1-SW)") (class "Default")
      (node (ref "C2") (pin "2") (pinfunction "2_2") (pintype "passive"))
      (node (ref "L2") (pin "1") (pinfunction "1_1") (pintype "bidirectional"))
      (node (ref "U1") (pin "5") (pinfunction "SW_5") (pintype "bidirectional"))
    )
    (net (code "55") (name "Net-(U2-Pad3)") (class "Default")
      (node (ref "U2") (pin "3") (pinfunction "3_3") (pintype "bidirectional"))
      (node (ref "U2") (pin "4") (pinfunction "4_4") (pintype "bidirectional"))
    )
    (net (code "56") (name "Net-(USB-CC1)") (class "Default")
      (node (ref "R28") (pin "2") (pinfunction "2_2") (pintype "passive"))
      (node (ref "USB") (pin "A5") (pinfunction "CC1_A5") (pintype "bidirectional"))
    )
    (net (code "57") (name "Net-(USB-CC2)") (class "Default")
      (node (ref "R29") (pin "2") (pinfunction "2_2") (pintype "passive"))
      (node (ref "USB") (pin "B5") (pinfunction "CC2_B5") (pintype "bidirectional"))
    )
    (net (code "58") (name "Net-(USB-DN1)") (class "Default")
      (node (ref "R27") (pin "1") (pinfunction "1_1") (pintype "passive"))
      (node (ref "USB") (pin "A7") (pinfunction "DN1_A7") (pintype "bidirectional"))
      (node (ref "USB") (pin "B7") (pinfunction "DN2_B7") (pintype "bidirectional"))
    )
    (net (code "59") (name "Net-(USB-DP1)") (class "Default")
      (node (ref "R26") (pin "1") (pinfunction "1_1") (pintype "passive"))
      (node (ref "USB") (pin "A6") (pinfunction "DP1_A6") (pintype "bidirectional"))
      (node (ref "USB") (pin "B6") (pinfunction "DP2_B6") (pintype "bidirectional"))
    )
    (net (code "60") (name "PWM") (class "Default")
      (node (ref "IC3") (pin "39") (pinfunction "PC8_39") (pintype "bidirectional"))
    )
    (net (code "61") (name "RST") (class "Default")
      (node (ref "C22") (pin "1") (pinfunction "1_1") (pintype "passive"))
      (node (ref "IC3") (pin "7") (pinfunction "NRST_7") (pintype "bidirectional"))
      (node (ref "R5") (pin "1") (pinfunction "1_1") (pintype "passive"))
      (node (ref "RST") (pin "3") (pinfunction "3_3") (pintype "passive"))
      (node (ref "RST") (pin "4") (pinfunction "4_4") (pintype "passive"))
      (node (ref "SWD") (pin "3") (pinfunction "RST_3") (pintype "bidirectional"))
      (node (ref "SWD_STLINK") (pin "12") (pinfunction "12_12") (pintype "bidirectional"))
    )
    (net (code "62") (name "SPI1_MISO") (class "Default")
      (node (ref "IC3") (pin "22") (pinfunction "PA6_22") (pintype "bidirectional"))
    )
    (net (code "63") (name "SPI1_MOSI") (class "Default")
      (node (ref "IC3") (pin "23") (pinfunction "PA7_23") (pintype "bidirectional"))
    )
    (net (code "64") (name "SPI1_SCLK") (class "Default")
      (node (ref "IC3") (pin "21") (pinfunction "PA5_21") (pintype "bidirectional"))
    )
    (net (code "65") (name "STAT") (class "Default")
      (node (ref "IC3") (pin "27") (pinfunction "PB1_27") (pintype "bidirectional"))
      (node (ref "R31") (pin "1") (pinfunction "1_1") (pintype "passive"))
    )
    (net (code "66") (name "SW") (class "Default")
      (node (ref "C23") (pin "1") (pinfunction "1_1") (pintype "passive"))
      (node (ref "IC3") (pin "4") (pinfunction "PC15_4") (pintype "bidirectional"))
      (node (ref "R3") (pin "1") (pinfunction "1_1") (pintype "passive"))
      (node (ref "SW") (pin "1") (pinfunction "COM_1") (pintype "bidirectional"))
    )
    (net (code "67") (name "SWCLK") (class "Default")
      (node (ref "IC3") (pin "49") (pinfunction "PA14_49") (pintype "bidirectional"))
      (node (ref "SWD") (pin "4") (pinfunction "SWCLK_4") (pintype "bidirectional"))
      (node (ref "SWD_STLINK") (pin "6") (pinfunction "6_6") (pintype "bidirectional"))
    )
    (net (code "68") (name "SWDIO") (class "Default")
      (node (ref "IC3") (pin "46") (pinfunction "PA13_46") (pintype "bidirectional"))
      (node (ref "SWD") (pin "2") (pinfunction "SWDIO_2") (pintype "bidirectional"))
      (node (ref "SWD_STLINK") (pin "4") (pinfunction "4_4") (pintype "bidirectional"))
    )
    (net (code "69") (name "SWO") (class "Default")
      (node (ref "IC3") (pin "55") (pinfunction "PB3_55") (pintype "bidirectional"))
      (node (ref "SWD") (pin "6") (pinfunction "SWO_6") (pintype "bidirectional"))
    )
    (net (code "70") (name "UART1_RX") (class "Default")
      (node (ref "IC3") (pin "43") (pinfunction "PA10_43") (pintype "bidirectional"))
    )
    (net (code "71") (name "UART1_TX") (class "Default")
      (node (ref "IC3") (pin "42") (pinfunction "PA9_42") (pintype "bidirectional"))
    )
    (net (code "72") (name "USB_DM") (class "Default")
      (node (ref "IC3") (pin "44") (pinfunction "PA11_44") (pintype "bidirectional"))
      (node (ref "R27") (pin "2") (pinfunction "2_2") (pintype "passive"))
    )
    (net (code "73") (name "USB_DP") (class "Default")
      (node (ref "IC3") (pin "45") (pinfunction "PA12_45") (pintype "bidirectional"))
      (node (ref "R26") (pin "2") (pinfunction "2_2") (pintype "passive"))
    )
    (net (code "74") (name "VBAT1") (class "Default")
      (node (ref "C25") (pin "2") (pinfunction "2_2") (pintype "passive"))
      (node (ref "IC2") (pin "10") (pinfunction "BAT_10") (pintype "bidirectional"))
      (node (ref "IC5") (pin "1") (pinfunction "IP+_1_1") (pintype "bidirectional"))
      (node (ref "IC5") (pin "2") (pinfunction "IP+_2_2") (pintype "bidirectional"))
      (node (ref "R23") (pin "2") (pinfunction "2_2") (pintype "passive"))
      (node (ref "R7") (pin "2") (pinfunction "2_2") (pintype "passive"))
      (node (ref "U2") (pin "1") (pinfunction "1_1") (pintype "bidirectional"))
    )
    (net (code "75") (name "VBAT2") (class "Default")
      (node (ref "C26") (pin "2") (pinfunction "2_2") (pintype "passive"))
      (node (ref "IC4") (pin "1") (pinfunction "VIN_1") (pintype "bidirectional"))
      (node (ref "IC5") (pin "3") (pinfunction "IP-_1_3") (pintype "bidirectional"))
      (node (ref "IC5") (pin "4") (pinfunction "IP-_2_4") (pintype "bidirectional"))
      (node (ref "L1") (pin "2") (pinfunction "2_2") (pintype "bidirectional"))
    )
    (net (code "76") (name "VCC") (class "Default")
      (node (ref "C16") (pin "1") (pinfunction "1_1") (pintype "passive"))
      (node (ref "D2") (pin "C") (pinfunction "C_C") (pintype "passive"))
      (node (ref "IC1") (pin "8") (pinfunction "VS_8") (pintype "bidirectional"))
      (node (ref "J2") (pin "1") (pinfunction "POWER_1") (pintype "bidirectional"))
      (node (ref "J3") (pin "1") (pinfunction "POWER_1") (pintype "bidirectional"))
      (node (ref "Q2") (pin "2") (pinfunction "D_2") (pintype "bidirectional"))
      (node (ref "Q3") (pin "2") (pinfunction "D_2") (pintype "bidirectional"))
      (node (ref "U1") (pin "2") (pinfunction "EN_2") (pintype "bidirectional"))
      (node (ref "U1") (pin "3") (pinfunction "VIN_3") (pintype "bidirectional"))
    )
    (net (code "77") (name "unconnected-(IC1-~{H2}-Pad5)") (class "Default")
      (node (ref "IC1") (pin "5") (pinfunction "~{H2}_5") (pintype "bidirectional"))
    )
    (net (code "78") (name "unconnected-(IC3-PA3-Pad17)") (class "Default")
      (node (ref "IC3") (pin "17") (pinfunction "PA3_17") (pintype "bidirectional"))
    )
    (net (code "79") (name "unconnected-(IC3-PA4-Pad20)") (class "Default")
      (node (ref "IC3") (pin "20") (pinfunction "PA4_20") (pintype "bidirectional"))
    )
    (net (code "80") (name "unconnected-(IC3-PA15-Pad50)") (class "Default")
      (node (ref "IC3") (pin "50") (pinfunction "PA15_50") (pintype "bidirectional"))
    )
    (net (code "81") (name "unconnected-(IC3-PB0-Pad26)") (class "Default")
      (node (ref "IC3") (pin "26") (pinfunction "PB0_26") (pintype "bidirectional"))
    )
    (net (code "82") (name "unconnected-(IC3-PB2-Pad28)") (class "Default")
      (node (ref "IC3") (pin "28") (pinfunction "PB2_28") (pintype "bidirectional"))
    )
    (net (code "83") (name "unconnected-(IC3-PB4-Pad56)") (class "Default")
      (node (ref "IC3") (pin "56") (pinfunction "PB4_56") (pintype "bidirectional"))
    )
    (net (code "84") (name "unconnected-(IC3-PB5-Pad57)") (class "Default")
      (node (ref "IC3") (pin "57") (pinfunction "PB5_57") (pintype "bidirectional"))
    )
    (net (code "85") (name "unconnected-(IC3-PB8-Pad61)") (class "Default")
      (node (ref "IC3") (pin "61") (pinfunction "PB8_61") (pintype "bidirectional"))
    )
    (net (code "86") (name "unconnected-(IC3-PB9-Pad62)") (class "Default")
      (node (ref "IC3") (pin "62") (pinfunction "PB9_62") (pintype "bidirectional"))
    )
    (net (code "87") (name "unconnected-(IC3-PB10-Pad29)") (class "Default")
      (node (ref "IC3") (pin "29") (pinfunction "PB10_29") (pintype "bidirectional"))
    )
    (net (code "88") (name "unconnected-(IC3-PB11-Pad30)") (class "Default")
      (node (ref "IC3") (pin "30") (pinfunction "PB11_30") (pintype "bidirectional"))
    )
    (net (code "89") (name "unconnected-(IC3-PC0-Pad8)") (class "Default")
      (node (ref "IC3") (pin "8") (pinfunction "PC0_8") (pintype "bidirectional"))
    )
    (net (code "90") (name "unconnected-(IC3-PC1-Pad9)") (class "Default")
      (node (ref "IC3") (pin "9") (pinfunction "PC1_9") (pintype "bidirectional"))
    )
    (net (code "91") (name "unconnected-(IC3-PC2-Pad10)") (class "Default")
      (node (ref "IC3") (pin "10") (pinfunction "PC2_10") (pintype "bidirectional"))
    )
    (net (code "92") (name "unconnected-(IC3-PC3-Pad11)") (class "Default")
      (node (ref "IC3") (pin "11") (pinfunction "PC3_11") (pintype "bidirectional"))
    )
    (net (code "93") (name "unconnected-(IC3-PC4-Pad24)") (class "Default")
      (node (ref "IC3") (pin "24") (pinfunction "PC4_24") (pintype "bidirectional"))
    )
    (net (code "94") (name "unconnected-(IC3-PC5-Pad25)") (class "Default")
      (node (ref "IC3") (pin "25") (pinfunction "PC5_25") (pintype "bidirectional"))
    )
    (net (code "95") (name "unconnected-(IC3-PC10-Pad51)") (class "Default")
      (node (ref "IC3") (pin "51") (pinfunction "PC10_51") (pintype "bidirectional"))
    )
    (net (code "96") (name "unconnected-(IC3-PC11-Pad52)") (class "Default")
      (node (ref "IC3") (pin "52") (pinfunction "PC11_52") (pintype "bidirectional"))
    )
    (net (code "97") (name "unconnected-(IC3-PC12-Pad53)") (class "Default")
      (node (ref "IC3") (pin "53") (pinfunction "PC12_53") (pintype "bidirectional"))
    )
    (net (code "98") (name "unconnected-(IC3-PC14-Pad3)") (class "Default")
      (node (ref "IC3") (pin "3") (pinfunction "PC14_3") (pintype "bidirectional"))
    )
    (net (code "99") (name "unconnected-(IC3-PD2-Pad54)") (class "Default")
      (node (ref "IC3") (pin "54") (pinfunction "PD2_54") (pintype "bidirectional"))
    )
    (net (code "100") (name "unconnected-(IC4-MODE_{slash}SYNC-Pad5)") (class "Default")
      (node (ref "IC4") (pin "5") (pinfunction "MODE_/SYNC_5") (pintype "bidirectional"))
    )
    (net (code "101") (name "unconnected-(RST-Pad5)") (class "Default")
      (node (ref "RST") (pin "5") (pinfunction "5_5") (pintype "passive"))
    )
    (net (code "102") (name "unconnected-(SWD_STLINK-Pad1)") (class "Default")
      (node (ref "SWD_STLINK") (pin "1") (pinfunction "1_1") (pintype "bidirectional"))
    )
    (net (code "103") (name "unconnected-(SWD_STLINK-Pad2)") (class "Default")
      (node (ref "SWD_STLINK") (pin "2") (pinfunction "2_2") (pintype "bidirectional"))
    )
    (net (code "104") (name "unconnected-(SWD_STLINK-Pad8)") (class "Default")
      (node (ref "SWD_STLINK") (pin "8") (pinfunction "8_8") (pintype "bidirectional"))
    )
    (net (code "105") (name "unconnected-(SWD_STLINK-Pad9)") (class "Default")
      (node (ref "SWD_STLINK") (pin "9") (pinfunction "9_9") (pintype "bidirectional"))
    )
    (net (code "106") (name "unconnected-(SWD_STLINK-Pad10)") (class "Default")
      (node (ref "SWD_STLINK") (pin "10") (pinfunction "10_10") (pintype "bidirectional"))
    )
    (net (code "107") (name "unconnected-(SWD_STLINK-Pad13)") (class "Default")
      (node (ref "SWD_STLINK") (pin "13") (pinfunction "13_13") (pintype "bidirectional"))
    )
    (net (code "108") (name "unconnected-(SWD_STLINK-Pad14)") (class "Default")
      (node (ref "SWD_STLINK") (pin "14") (pinfunction "14_14") (pintype "bidirectional"))
    )
    (net (code "109") (name "unconnected-(USB-SBU1-PadA8)") (class "Default")
      (node (ref "USB") (pin "A8") (pinfunction "SBU1_A8") (pintype "bidirectional"))
    )
    (net (code "110") (name "unconnected-(USB-SBU2-PadB8)") (class "Default")
      (node (ref "USB") (pin "B8") (pinfunction "SBU2_B8") (pintype "bidirectional"))
    )
  )
)
